# micro.net
KiCad netlist of a schematic drawn in Altium Designer
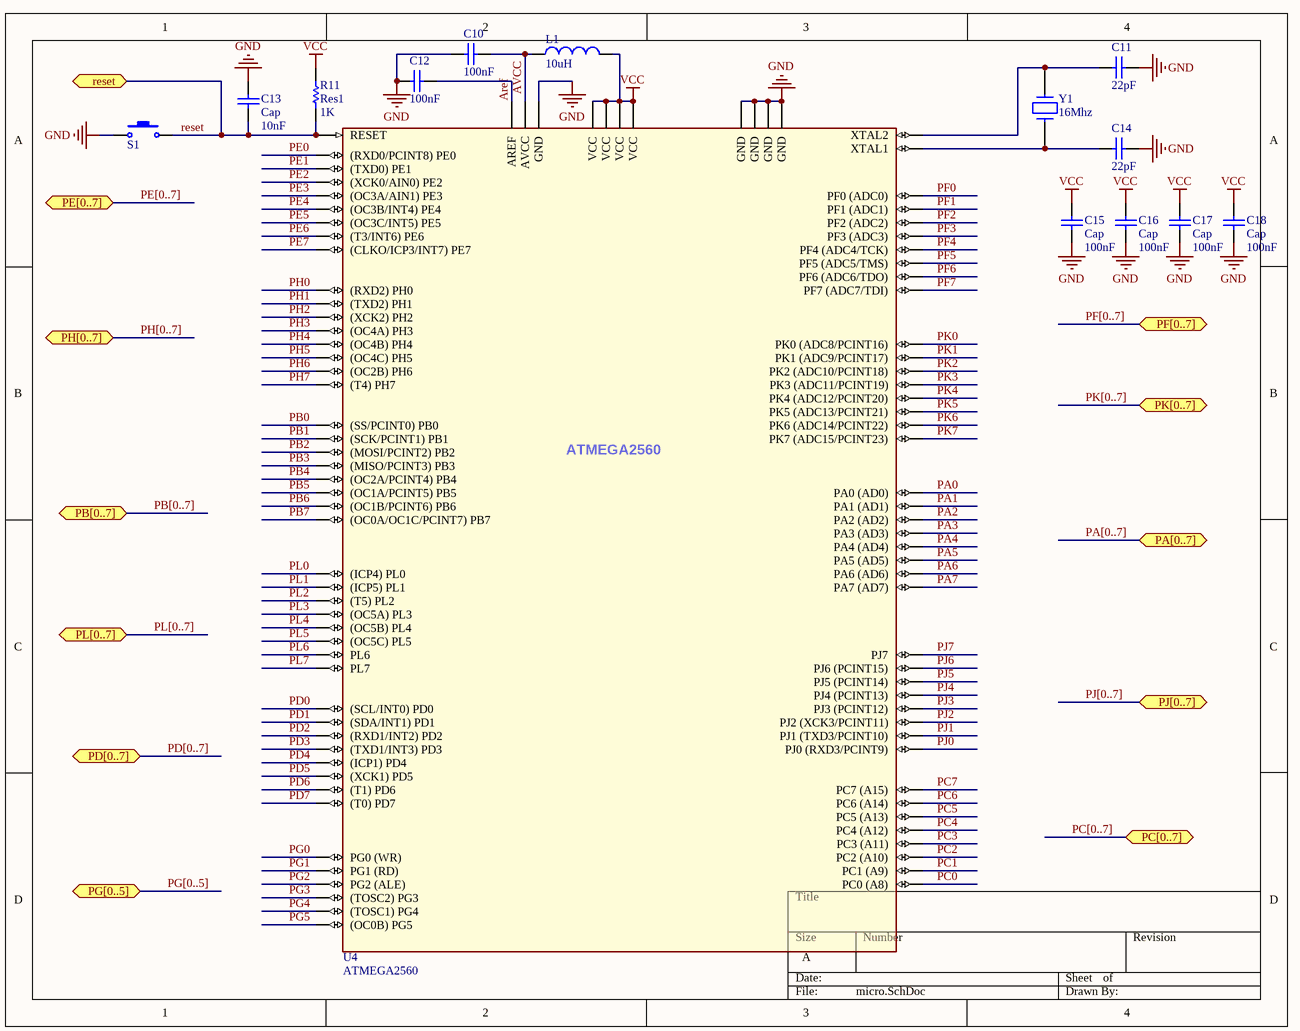
[diagram p0: micro.SchDoc]

(export (version "E")
  (design (tool "Eeschema 10.0.6"))
  (components
    (comp (ref "C10")
      (value "100nF")
      (footprint "CAP 1206 (3216X15L)")
      (description "CAP-100Nf")
      (fields (field (name "Comment") "Cap"))
      (libsource (lib "Altium library (www.AVRelec.com)") (part "Cap ceramic"))
    )
    (comp (ref "C11")
      (value "22pF")
      (footprint "CAP 1206 (3216X15L)")
      (description "CAP-100Nf")
      (fields (field (name "Comment") "Cap"))
      (libsource (lib "Altium library (www.AVRelec.com)") (part "Cap ceramic"))
    )
    (comp (ref "C12")
      (value "100nF")
      (footprint "CAP 1206 (3216X15L)")
      (description "CAP-100Nf")
      (fields (field (name "Comment") "Cap"))
      (libsource (lib "Altium library (www.AVRelec.com)") (part "Cap ceramic"))
    )
    (comp (ref "C13")
      (value "Cap")
      (footprint "CAP 1206 (3216X15L)")
      (description "CAP-100Nf")
      (fields (field (name "ALTIUM_VALUE") "10nF"))
      (libsource (lib "Altium library (www.AVRelec.com)") (part "Cap ceramic"))
    )
    (comp (ref "C14")
      (value "22pF")
      (footprint "CAP 1206 (3216X15L)")
      (description "CAP-100Nf")
      (fields (field (name "Comment") "Cap"))
      (libsource (lib "Altium library (www.AVRelec.com)") (part "Cap ceramic"))
    )
    (comp (ref "C15")
      (value "Cap")
      (footprint "CAP 1206 (3216X15L)")
      (description "CAP-100Nf")
      (fields (field (name "ALTIUM_VALUE") "100nF"))
      (libsource (lib "Altium library (www.AVRelec.com)") (part "Cap ceramic"))
    )
    (comp (ref "C16")
      (value "Cap")
      (footprint "CAP 1206 (3216X15L)")
      (description "CAP-100Nf")
      (fields (field (name "ALTIUM_VALUE") "100nF"))
      (libsource (lib "Altium library (www.AVRelec.com)") (part "Cap ceramic"))
    )
    (comp (ref "C17")
      (value "Cap")
      (footprint "CAP 1206 (3216X15L)")
      (description "CAP-100Nf")
      (fields (field (name "ALTIUM_VALUE") "100nF"))
      (libsource (lib "Altium library (www.AVRelec.com)") (part "Cap ceramic"))
    )
    (comp (ref "C18")
      (value "Cap")
      (footprint "CAP 1206 (3216X15L)")
      (description "CAP-100Nf")
      (fields (field (name "ALTIUM_VALUE") "100nF"))
      (libsource (lib "Altium library (www.AVRelec.com)") (part "Cap ceramic"))
    )
    (comp (ref "L1")
      (value "10uH")
      (footprint "IND1206")
      (description "Inductor")
      (fields (field (name "PUBLISHER") "Altium Limited"))
      (libsource (lib "Miscellaneous Devices") (part "Inductor"))
    )
    (comp (ref "R11")
      (value "Res1")
      (footprint "RES 1206 (3216X08L)")
      (description "Resistor")
      (fields (field (name "ALTIUM_VALUE") "1K") (field (name "PUBLISHER") "Altium Limited"))
      (libsource (lib "Miscellaneous Devices") (part "Res1"))
    )
    (comp (ref "S1")
      (value "Switch PB")
      (footprint "Switch - Push to On")
      (description "Push Button Switch")
      (libsource (lib "Altium (2)") (part "Switch PB"))
    )
    (comp (ref "U4")
      (value "ATMEGA2560")
      (footprint "MY_ATMEGA2560")
      (description "AVR 256K Bytes of In-System Programmable Flash Memory")
      (libsource (lib "Altium library (www.AVRelec.com)") (part "ATMEGA2560"))
    )
    (comp (ref "Y1")
      (value "16Mhz")
      (footprint "My_Crystal")
      (description "Crystal")
      (libsource (lib "Altium library (www.AVRelec.com)") (part "CRYSTAL"))
    )
  )
  (nets
    (net (code "1") (name "/AVCC") (class "Default")
      (node (ref "C10") (pin "2") (pinfunction "2_2") (pintype "passive"))
      (node (ref "L1") (pin "1") (pinfunction "1_1") (pintype "passive"))
      (node (ref "U4") (pin "100") (pinfunction "AVCC_100") (pintype "power_in"))
    )
    (net (code "2") (name "/Aref") (class "Default")
      (node (ref "C12") (pin "2") (pinfunction "2_2") (pintype "passive"))
      (node (ref "U4") (pin "98") (pinfunction "AREF_98") (pintype "passive"))
    )
    (net (code "3") (name "/PA0") (class "Default")
      (node (ref "U4") (pin "78") (pinfunction "PA0_(AD0)_78") (pintype "bidirectional"))
    )
    (net (code "4") (name "/PA1") (class "Default")
      (node (ref "U4") (pin "77") (pinfunction "PA1_(AD1)_77") (pintype "bidirectional"))
    )
    (net (code "5") (name "/PA2") (class "Default")
      (node (ref "U4") (pin "76") (pinfunction "PA2_(AD2)_76") (pintype "bidirectional"))
    )
    (net (code "6") (name "/PA3") (class "Default")
      (node (ref "U4") (pin "75") (pinfunction "PA3_(AD3)_75") (pintype "bidirectional"))
    )
    (net (code "7") (name "/PA4") (class "Default")
      (node (ref "U4") (pin "74") (pinfunction "PA4_(AD4)_74") (pintype "bidirectional"))
    )
    (net (code "8") (name "/PA5") (class "Default")
      (node (ref "U4") (pin "73") (pinfunction "PA5_(AD5)_73") (pintype "bidirectional"))
    )
    (net (code "9") (name "/PA6") (class "Default")
      (node (ref "U4") (pin "72") (pinfunction "PA6_(AD6)_72") (pintype "bidirectional"))
    )
    (net (code "10") (name "/PA7") (class "Default")
      (node (ref "U4") (pin "71") (pinfunction "PA7_(AD7)_71") (pintype "bidirectional"))
    )
    (net (code "12") (name "/PB0") (class "Default")
      (node (ref "U4") (pin "19") (pinfunction "(SS/PCINT0)_PB0_19") (pintype "bidirectional"))
    )
    (net (code "13") (name "/PB1") (class "Default")
      (node (ref "U4") (pin "20") (pinfunction "(SCK/PCINT1)_PB1_20") (pintype "bidirectional"))
    )
    (net (code "14") (name "/PB2") (class "Default")
      (node (ref "U4") (pin "21") (pinfunction "(MOSI/PCINT2)_PB2_21") (pintype "bidirectional"))
    )
    (net (code "15") (name "/PB3") (class "Default")
      (node (ref "U4") (pin "22") (pinfunction "(MISO/PCINT3)_PB3_22") (pintype "bidirectional"))
    )
    (net (code "16") (name "/PB4") (class "Default")
      (node (ref "U4") (pin "23") (pinfunction "(OC2A/PCINT4)_PB4_23") (pintype "bidirectional"))
    )
    (net (code "17") (name "/PB5") (class "Default")
      (node (ref "U4") (pin "24") (pinfunction "(OC1A/PCINT5)_PB5_24") (pintype "bidirectional"))
    )
    (net (code "18") (name "/PB6") (class "Default")
      (node (ref "U4") (pin "25") (pinfunction "(OC1B/PCINT6)_PB6_25") (pintype "bidirectional"))
    )
    (net (code "19") (name "/PB7") (class "Default")
      (node (ref "U4") (pin "26") (pinfunction "(OC0A/OC1C/PCINT7)_PB7_26") (pintype "bidirectional"))
    )
    (net (code "21") (name "/PC0") (class "Default")
      (node (ref "U4") (pin "53") (pinfunction "PC0_(A8)_53") (pintype "bidirectional"))
    )
    (net (code "22") (name "/PC1") (class "Default")
      (node (ref "U4") (pin "54") (pinfunction "PC1_(A9)_54") (pintype "bidirectional"))
    )
    (net (code "23") (name "/PC2") (class "Default")
      (node (ref "U4") (pin "55") (pinfunction "PC2_(A10)_55") (pintype "bidirectional"))
    )
    (net (code "24") (name "/PC3") (class "Default")
      (node (ref "U4") (pin "56") (pinfunction "PC3_(A11)_56") (pintype "bidirectional"))
    )
    (net (code "25") (name "/PC4") (class "Default")
      (node (ref "U4") (pin "57") (pinfunction "PC4_(A12)_57") (pintype "bidirectional"))
    )
    (net (code "26") (name "/PC5") (class "Default")
      (node (ref "U4") (pin "58") (pinfunction "PC5_(A13)_58") (pintype "bidirectional"))
    )
    (net (code "27") (name "/PC6") (class "Default")
      (node (ref "U4") (pin "59") (pinfunction "PC6_(A14)_59") (pintype "bidirectional"))
    )
    (net (code "28") (name "/PC7") (class "Default")
      (node (ref "U4") (pin "60") (pinfunction "PC7_(A15)_60") (pintype "bidirectional"))
    )
    (net (code "30") (name "/PD0") (class "Default")
      (node (ref "U4") (pin "43") (pinfunction "(SCL/INT0)_PD0_43") (pintype "bidirectional"))
    )
    (net (code "31") (name "/PD1") (class "Default")
      (node (ref "U4") (pin "44") (pinfunction "(SDA/INT1)_PD1_44") (pintype "bidirectional"))
    )
    (net (code "32") (name "/PD2") (class "Default")
      (node (ref "U4") (pin "45") (pinfunction "(RXD1/INT2)_PD2_45") (pintype "bidirectional"))
    )
    (net (code "33") (name "/PD3") (class "Default")
      (node (ref "U4") (pin "46") (pinfunction "(TXD1/INT3)_PD3_46") (pintype "bidirectional"))
    )
    (net (code "34") (name "/PD4") (class "Default")
      (node (ref "U4") (pin "47") (pinfunction "(ICP1)_PD4_47") (pintype "bidirectional"))
    )
    (net (code "35") (name "/PD5") (class "Default")
      (node (ref "U4") (pin "48") (pinfunction "(XCK1)_PD5_48") (pintype "bidirectional"))
    )
    (net (code "36") (name "/PD6") (class "Default")
      (node (ref "U4") (pin "49") (pinfunction "(T1)_PD6_49") (pintype "bidirectional"))
    )
    (net (code "37") (name "/PD7") (class "Default")
      (node (ref "U4") (pin "50") (pinfunction "(T0)_PD7_50") (pintype "bidirectional"))
    )
    (net (code "39") (name "/PE0") (class "Default")
      (node (ref "U4") (pin "2") (pinfunction "(RXD0/PCINT8)_PE0_2") (pintype "bidirectional"))
    )
    (net (code "40") (name "/PE1") (class "Default")
      (node (ref "U4") (pin "3") (pinfunction "(TXD0)_PE1_3") (pintype "bidirectional"))
    )
    (net (code "41") (name "/PE2") (class "Default")
      (node (ref "U4") (pin "4") (pinfunction "(XCK0/AIN0)_PE2_4") (pintype "bidirectional"))
    )
    (net (code "42") (name "/PE3") (class "Default")
      (node (ref "U4") (pin "5") (pinfunction "(OC3A/AIN1)_PE3_5") (pintype "bidirectional"))
    )
    (net (code "43") (name "/PE4") (class "Default")
      (node (ref "U4") (pin "6") (pinfunction "(OC3B/INT4)_PE4_6") (pintype "bidirectional"))
    )
    (net (code "44") (name "/PE5") (class "Default")
      (node (ref "U4") (pin "7") (pinfunction "(OC3C/INT5)_PE5_7") (pintype "bidirectional"))
    )
    (net (code "45") (name "/PE6") (class "Default")
      (node (ref "U4") (pin "8") (pinfunction "(T3/INT6)_PE6_8") (pintype "bidirectional"))
    )
    (net (code "46") (name "/PE7") (class "Default")
      (node (ref "U4") (pin "9") (pinfunction "(CLKO/ICP3/INT7)_PE7_9") (pintype "bidirectional"))
    )
    (net (code "48") (name "/PF0") (class "Default")
      (node (ref "U4") (pin "97") (pinfunction "PF0_(ADC0)_97") (pintype "bidirectional"))
    )
    (net (code "49") (name "/PF1") (class "Default")
      (node (ref "U4") (pin "96") (pinfunction "PF1_(ADC1)_96") (pintype "bidirectional"))
    )
    (net (code "50") (name "/PF2") (class "Default")
      (node (ref "U4") (pin "95") (pinfunction "PF2_(ADC2)_95") (pintype "bidirectional"))
    )
    (net (code "51") (name "/PF3") (class "Default")
      (node (ref "U4") (pin "94") (pinfunction "PF3_(ADC3)_94") (pintype "bidirectional"))
    )
    (net (code "52") (name "/PF4") (class "Default")
      (node (ref "U4") (pin "93") (pinfunction "PF4_(ADC4/TCK)_93") (pintype "bidirectional"))
    )
    (net (code "53") (name "/PF5") (class "Default")
      (node (ref "U4") (pin "92") (pinfunction "PF5_(ADC5/TMS)_92") (pintype "bidirectional"))
    )
    (net (code "54") (name "/PF6") (class "Default")
      (node (ref "U4") (pin "91") (pinfunction "PF6_(ADC6/TDO)_91") (pintype "bidirectional"))
    )
    (net (code "55") (name "/PF7") (class "Default")
      (node (ref "U4") (pin "90") (pinfunction "PF7_(ADC7/TDI)_90") (pintype "bidirectional"))
    )
    (net (code "57") (name "/PG0") (class "Default")
      (node (ref "U4") (pin "51") (pinfunction "PG0_(WR)_51") (pintype "bidirectional"))
    )
    (net (code "58") (name "/PG1") (class "Default")
      (node (ref "U4") (pin "52") (pinfunction "PG1_(RD)_52") (pintype "bidirectional"))
    )
    (net (code "59") (name "/PG2") (class "Default")
      (node (ref "U4") (pin "70") (pinfunction "PG2_(ALE)_70") (pintype "bidirectional"))
    )
    (net (code "60") (name "/PG3") (class "Default")
      (node (ref "U4") (pin "28") (pinfunction "(TOSC2)_PG3_28") (pintype "bidirectional"))
    )
    (net (code "61") (name "/PG4") (class "Default")
      (node (ref "U4") (pin "29") (pinfunction "(TOSC1)_PG4_29") (pintype "bidirectional"))
    )
    (net (code "62") (name "/PG5") (class "Default")
      (node (ref "U4") (pin "1") (pinfunction "(OC0B)_PG5_1") (pintype "bidirectional"))
    )
    (net (code "64") (name "/PH0") (class "Default")
      (node (ref "U4") (pin "12") (pinfunction "(RXD2)_PH0_12") (pintype "bidirectional"))
    )
    (net (code "65") (name "/PH1") (class "Default")
      (node (ref "U4") (pin "13") (pinfunction "(TXD2)_PH1_13") (pintype "bidirectional"))
    )
    (net (code "66") (name "/PH2") (class "Default")
      (node (ref "U4") (pin "14") (pinfunction "(XCK2)_PH2_14") (pintype "bidirectional"))
    )
    (net (code "67") (name "/PH3") (class "Default")
      (node (ref "U4") (pin "15") (pinfunction "(OC4A)_PH3_15") (pintype "bidirectional"))
    )
    (net (code "68") (name "/PH4") (class "Default")
      (node (ref "U4") (pin "16") (pinfunction "(OC4B)_PH4_16") (pintype "bidirectional"))
    )
    (net (code "69") (name "/PH5") (class "Default")
      (node (ref "U4") (pin "17") (pinfunction "(OC4C)_PH5_17") (pintype "bidirectional"))
    )
    (net (code "70") (name "/PH6") (class "Default")
      (node (ref "U4") (pin "18") (pinfunction "(OC2B)_PH6_18") (pintype "bidirectional"))
    )
    (net (code "71") (name "/PH7") (class "Default")
      (node (ref "U4") (pin "27") (pinfunction "(T4)_PH7_27") (pintype "bidirectional"))
    )
    (net (code "73") (name "/PJ0") (class "Default")
      (node (ref "U4") (pin "63") (pinfunction "PJ0_(RXD3/PCINT9)_63") (pintype "bidirectional"))
    )
    (net (code "74") (name "/PJ1") (class "Default")
      (node (ref "U4") (pin "64") (pinfunction "PJ1_(TXD3/PCINT10)_64") (pintype "bidirectional"))
    )
    (net (code "75") (name "/PJ2") (class "Default")
      (node (ref "U4") (pin "65") (pinfunction "PJ2_(XCK3/PCINT11)_65") (pintype "bidirectional"))
    )
    (net (code "76") (name "/PJ3") (class "Default")
      (node (ref "U4") (pin "66") (pinfunction "PJ3_(PCINT12)_66") (pintype "bidirectional"))
    )
    (net (code "77") (name "/PJ4") (class "Default")
      (node (ref "U4") (pin "67") (pinfunction "PJ4_(PCINT13)_67") (pintype "bidirectional"))
    )
    (net (code "78") (name "/PJ5") (class "Default")
      (node (ref "U4") (pin "68") (pinfunction "PJ5_(PCINT14)_68") (pintype "bidirectional"))
    )
    (net (code "79") (name "/PJ6") (class "Default")
      (node (ref "U4") (pin "69") (pinfunction "PJ6_(PCINT15)_69") (pintype "bidirectional"))
    )
    (net (code "80") (name "/PJ7") (class "Default")
      (node (ref "U4") (pin "79") (pinfunction "PJ7_79") (pintype "bidirectional"))
    )
    (net (code "82") (name "/PK0") (class "Default")
      (node (ref "U4") (pin "89") (pinfunction "PK0_(ADC8/PCINT16)_89") (pintype "bidirectional"))
    )
    (net (code "83") (name "/PK1") (class "Default")
      (node (ref "U4") (pin "88") (pinfunction "PK1_(ADC9/PCINT17)_88") (pintype "bidirectional"))
    )
    (net (code "84") (name "/PK2") (class "Default")
      (node (ref "U4") (pin "87") (pinfunction "PK2_(ADC10/PCINT18)_87") (pintype "bidirectional"))
    )
    (net (code "85") (name "/PK3") (class "Default")
      (node (ref "U4") (pin "86") (pinfunction "PK3_(ADC11/PCINT19)_86") (pintype "bidirectional"))
    )
    (net (code "86") (name "/PK4") (class "Default")
      (node (ref "U4") (pin "85") (pinfunction "PK4_(ADC12/PCINT20)_85") (pintype "bidirectional"))
    )
    (net (code "87") (name "/PK5") (class "Default")
      (node (ref "U4") (pin "84") (pinfunction "PK5_(ADC13/PCINT21)_84") (pintype "bidirectional"))
    )
    (net (code "88") (name "/PK6") (class "Default")
      (node (ref "U4") (pin "83") (pinfunction "PK6_(ADC14/PCINT22)_83") (pintype "bidirectional"))
    )
    (net (code "89") (name "/PK7") (class "Default")
      (node (ref "U4") (pin "82") (pinfunction "PK7_(ADC15/PCINT23)_82") (pintype "bidirectional"))
    )
    (net (code "91") (name "/PL0") (class "Default")
      (node (ref "U4") (pin "35") (pinfunction "(ICP4)_PL0_35") (pintype "bidirectional"))
    )
    (net (code "92") (name "/PL1") (class "Default")
      (node (ref "U4") (pin "36") (pinfunction "(ICP5)_PL1_36") (pintype "bidirectional"))
    )
    (net (code "93") (name "/PL2") (class "Default")
      (node (ref "U4") (pin "37") (pinfunction "(T5)_PL2_37") (pintype "bidirectional"))
    )
    (net (code "94") (name "/PL3") (class "Default")
      (node (ref "U4") (pin "38") (pinfunction "(OC5A)_PL3_38") (pintype "bidirectional"))
    )
    (net (code "95") (name "/PL4") (class "Default")
      (node (ref "U4") (pin "39") (pinfunction "(OC5B)_PL4_39") (pintype "bidirectional"))
    )
    (net (code "96") (name "/PL5") (class "Default")
      (node (ref "U4") (pin "40") (pinfunction "(OC5C)_PL5_40") (pintype "bidirectional"))
    )
    (net (code "97") (name "/PL6") (class "Default")
      (node (ref "U4") (pin "41") (pinfunction "PL6_41") (pintype "bidirectional"))
    )
    (net (code "98") (name "/PL7") (class "Default")
      (node (ref "U4") (pin "42") (pinfunction "PL7_42") (pintype "bidirectional"))
    )
    (net (code "100") (name "/reset") (class "Default")
      (node (ref "C13") (pin "1") (pinfunction "1_1") (pintype "passive"))
      (node (ref "R11") (pin "1") (pinfunction "1_1") (pintype "passive"))
      (node (ref "S1") (pin "2") (pinfunction "2_2") (pintype "passive"))
      (node (ref "U4") (pin "30") (pinfunction "RESET_30") (pintype "input"))
    )
    (net (code "101") (name "GND") (class "Default")
      (node (ref "C10") (pin "1") (pinfunction "1_1") (pintype "passive"))
      (node (ref "C11") (pin "2") (pinfunction "2_2") (pintype "passive"))
      (node (ref "C12") (pin "1") (pinfunction "1_1") (pintype "passive"))
      (node (ref "C13") (pin "2") (pinfunction "2_2") (pintype "passive"))
      (node (ref "C14") (pin "2") (pinfunction "2_2") (pintype "passive"))
      (node (ref "C15") (pin "1") (pinfunction "1_1") (pintype "passive"))
      (node (ref "C16") (pin "1") (pinfunction "1_1") (pintype "passive"))
      (node (ref "C17") (pin "1") (pinfunction "1_1") (pintype "passive"))
      (node (ref "C18") (pin "1") (pinfunction "1_1") (pintype "passive"))
      (node (ref "S1") (pin "1") (pinfunction "1_1") (pintype "passive"))
      (node (ref "U4") (pin "11") (pinfunction "GND_11") (pintype "power_in"))
      (node (ref "U4") (pin "32") (pinfunction "GND_32") (pintype "power_in"))
      (node (ref "U4") (pin "62") (pinfunction "GND_62") (pintype "power_in"))
      (node (ref "U4") (pin "81") (pinfunction "GND_81") (pintype "power_in"))
      (node (ref "U4") (pin "99") (pinfunction "GND_99") (pintype "power_in"))
    )
    (net (code "102") (name "Net-(U4-XTAL1)") (class "Default")
      (node (ref "C14") (pin "1") (pinfunction "1_1") (pintype "passive"))
      (node (ref "U4") (pin "34") (pinfunction "XTAL1_34") (pintype "bidirectional"))
      (node (ref "Y1") (pin "1") (pinfunction "1_1") (pintype "passive"))
    )
    (net (code "103") (name "Net-(U4-XTAL2)") (class "Default")
      (node (ref "C11") (pin "1") (pinfunction "1_1") (pintype "passive"))
      (node (ref "U4") (pin "33") (pinfunction "XTAL2_33") (pintype "bidirectional"))
      (node (ref "Y1") (pin "2") (pinfunction "2_2") (pintype "passive"))
    )
    (net (code "104") (name "VCC") (class "Default")
      (node (ref "C15") (pin "2") (pinfunction "2_2") (pintype "passive"))
      (node (ref "C16") (pin "2") (pinfunction "2_2") (pintype "passive"))
      (node (ref "C17") (pin "2") (pinfunction "2_2") (pintype "passive"))
      (node (ref "C18") (pin "2") (pinfunction "2_2") (pintype "passive"))
      (node (ref "L1") (pin "2") (pinfunction "2_2") (pintype "passive"))
      (node (ref "R11") (pin "2") (pinfunction "2_2") (pintype "passive"))
      (node (ref "U4") (pin "10") (pinfunction "VCC_10") (pintype "power_in"))
      (node (ref "U4") (pin "31") (pinfunction "VCC_31") (pintype "power_in"))
      (node (ref "U4") (pin "61") (pinfunction "VCC_61") (pintype "power_in"))
      (node (ref "U4") (pin "80") (pinfunction "VCC_80") (pintype "power_in"))
    )
  )
)
